# Sheet1.net
KiCad netlist of a schematic drawn in Altium Designer
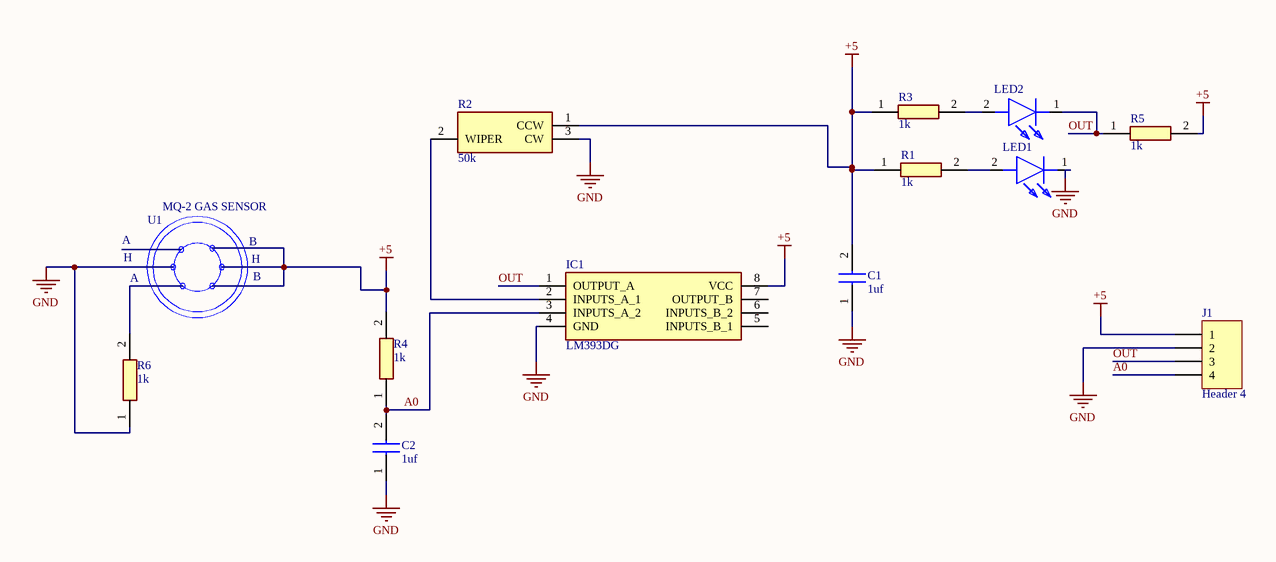
[diagram p0: Sheet1.SchDoc]

(export (version "E")
  (design (tool "Eeschema 10.0.6"))
  (components
    (comp (ref "C1")
      (value "1uf")
      (footprint "SamacSys:CAPC2012X145N")
      (description "Capacitor")
      (fields
        (field (name "MANUFACTURER_PART_NUMBER") "GRM21BR71H105KA12L")
        (field (name "MOUSER PART NUMBER") "81-GRM21BR71H105KA2L")
      )
      (libsource (lib "*") (part "GRM21BR71H105KA12L"))
    )
    (comp (ref "C2")
      (value "1uf")
      (footprint "SamacSys:CAPC2012X145N")
      (description "Capacitor")
      (fields
        (field (name "MANUFACTURER_PART_NUMBER") "GRM21BR71H105KA12L")
        (field (name "MOUSER PART NUMBER") "81-GRM21BR71H105KA2L")
      )
      (libsource (lib "*") (part "GRM21BR71H105KA12L"))
    )
    (comp (ref "IC1")
      (value "LM393DG")
      (footprint "SamacSys:SOIC127P600X175-8N")
      (description "Integrated Circuit")
      (fields (field (name "MOUSER PART NUMBER") "863-LM393DG"))
      (libsource (lib "*") (part "LM393DG"))
    )
    (comp (ref "J1")
      (value "Header 4")
      (footprint "HDR1X4")
      (description "Header, 4-Pin")
      (fields (field (name "PUBLISHER") "Altium Limited"))
      (libsource (lib "Miscellaneous Connectors") (part "Header 4"))
    )
    (comp (ref "LED1")
      (value "151031VS06000")
      (footprint "SamacSys:151034GS03000")
      (description "LED")
      (fields (field (name "MOUSER PART NUMBER") "710-151031VS06000"))
      (libsource (lib "*") (part "151031VS06000"))
    )
    (comp (ref "LED2")
      (value "151031VS06000")
      (footprint "SamacSys:151034GS03000")
      (description "LED")
      (fields (field (name "MOUSER PART NUMBER") "710-151031VS06000"))
      (libsource (lib "*") (part "151031VS06000"))
    )
    (comp (ref "R1")
      (value "1k")
      (footprint "SamacSys:RESC2012X60N")
      (description "Resistor")
      (fields
        (field (name "MANUFACTURER_PART_NUMBER") "RC0805FR-071KL")
        (field (name "MOUSER PART NUMBER") "603-RC0805FR-071KL")
      )
      (libsource (lib "*") (part "RC0805FR-071KL"))
    )
    (comp (ref "R2")
      (value "50k")
      (footprint "SamacSys:3386P_1")
      (description "Variable Resistor")
      (fields
        (field (name "MANUFACTURER_PART_NUMBER") "3386P-1-104LF")
        (field (name "MOUSER PART NUMBER") "652-3386P-1-104LF")
      )
      (libsource (lib "SamacSys") (part "3386P-1-104LF"))
    )
    (comp (ref "R3")
      (value "1k")
      (footprint "SamacSys:RESC2012X60N")
      (description "Resistor")
      (fields
        (field (name "MANUFACTURER_PART_NUMBER") "RC0805FR-071KL")
        (field (name "MOUSER PART NUMBER") "603-RC0805FR-071KL")
      )
      (libsource (lib "*") (part "RC0805FR-071KL"))
    )
    (comp (ref "R4")
      (value "1k")
      (footprint "SamacSys:RESC2012X60N")
      (description "Resistor")
      (fields
        (field (name "MANUFACTURER_PART_NUMBER") "RC0805FR-071KL")
        (field (name "MOUSER PART NUMBER") "603-RC0805FR-071KL")
      )
      (libsource (lib "") (part "RC0805FR-071KL_1"))
    )
    (comp (ref "R5")
      (value "1k")
      (footprint "SamacSys:RESC2012X60N")
      (description "Resistor")
      (fields
        (field (name "MANUFACTURER_PART_NUMBER") "RC0805FR-071KL")
        (field (name "MOUSER PART NUMBER") "603-RC0805FR-071KL")
      )
      (libsource (lib "*") (part "RC0805FR-071KL"))
    )
    (comp (ref "R6")
      (value "1k")
      (footprint "SamacSys:RESC2012X60N")
      (description "Resistor")
      (fields
        (field (name "MANUFACTURER_PART_NUMBER") "RC0805FR-071KL")
        (field (name "MOUSER PART NUMBER") "603-RC0805FR-071KL")
      )
      (libsource (lib "") (part "RC0805FR-071KL_1"))
    )
    (comp (ref "U1")
      (value "MQ-2 GAS SENSOR")
      (footprint "configuration")
      (libsource (lib "gas_sensor") (part "MQ-2"))
    )
  )
  (nets
    (net (code "1") (name "+5") (class "Default")
      (node (ref "C1") (pin "2") (pinfunction "2_2") (pintype "passive"))
      (node (ref "IC1") (pin "8") (pinfunction "VCC_8") (pintype "passive"))
      (node (ref "J1") (pin "1") (pinfunction "1_1") (pintype "passive"))
      (node (ref "R1") (pin "1") (pinfunction "1_1") (pintype "passive"))
      (node (ref "R2") (pin "1") (pinfunction "CCW_1") (pintype "passive"))
      (node (ref "R3") (pin "1") (pinfunction "1_1") (pintype "passive"))
      (node (ref "R4") (pin "2") (pinfunction "2_2") (pintype "passive"))
      (node (ref "R5") (pin "2") (pinfunction "2_2") (pintype "passive"))
    )
    (net (code "2") (name "/A0") (class "Default")
      (node (ref "C2") (pin "2") (pinfunction "2_2") (pintype "passive"))
      (node (ref "IC1") (pin "3") (pinfunction "INPUTS_A_2_3") (pintype "passive"))
      (node (ref "J1") (pin "4") (pinfunction "4_4") (pintype "passive"))
      (node (ref "R4") (pin "1") (pinfunction "1_1") (pintype "passive"))
    )
    (net (code "3") (name "/OUT") (class "Default")
      (node (ref "IC1") (pin "1") (pinfunction "OUTPUT_A_1") (pintype "passive"))
      (node (ref "J1") (pin "3") (pinfunction "3_3") (pintype "passive"))
      (node (ref "LED2") (pin "1") (pinfunction "K_1") (pintype "passive"))
      (node (ref "R5") (pin "1") (pinfunction "1_1") (pintype "passive"))
    )
    (net (code "4") (name "GND") (class "Default")
      (node (ref "C1") (pin "1") (pinfunction "1_1") (pintype "passive"))
      (node (ref "C2") (pin "1") (pinfunction "1_1") (pintype "passive"))
      (node (ref "IC1") (pin "4") (pinfunction "GND_4") (pintype "passive"))
      (node (ref "J1") (pin "2") (pinfunction "2_2") (pintype "passive"))
      (node (ref "LED1") (pin "1") (pinfunction "K_1") (pintype "passive"))
      (node (ref "R2") (pin "3") (pinfunction "CW_3") (pintype "passive"))
      (node (ref "R6") (pin "1") (pinfunction "1_1") (pintype "passive"))
    )
    (net (code "5") (name "Net-(IC1-INPUTS_A_1)") (class "Default")
      (node (ref "IC1") (pin "2") (pinfunction "INPUTS_A_1_2") (pintype "passive"))
      (node (ref "R2") (pin "2") (pinfunction "WIPER_2") (pintype "passive"))
    )
    (net (code "6") (name "Net-(LED1-A)") (class "Default")
      (node (ref "LED1") (pin "2") (pinfunction "A_2") (pintype "passive"))
      (node (ref "R1") (pin "2") (pinfunction "2_2") (pintype "passive"))
    )
    (net (code "7") (name "Net-(LED2-A)") (class "Default")
      (node (ref "LED2") (pin "2") (pinfunction "A_2") (pintype "passive"))
      (node (ref "R3") (pin "2") (pinfunction "2_2") (pintype "passive"))
    )
    (net (code "8") (name "unconnected-(IC1-INPUTS_B_1-Pad5)") (class "Default")
      (node (ref "IC1") (pin "5") (pinfunction "INPUTS_B_1_5") (pintype "passive"))
    )
    (net (code "9") (name "unconnected-(IC1-INPUTS_B_2-Pad6)") (class "Default")
      (node (ref "IC1") (pin "6") (pinfunction "INPUTS_B_2_6") (pintype "passive"))
    )
    (net (code "10") (name "unconnected-(IC1-OUTPUT_B-Pad7)") (class "Default")
      (node (ref "IC1") (pin "7") (pinfunction "OUTPUT_B_7") (pintype "passive"))
    )
    (net (code "11") (name "unconnected-(R6-Pad2)") (class "Default")
      (node (ref "R6") (pin "2") (pinfunction "2_2") (pintype "passive"))
    )
  )
)
